# Schematic_-_Power_Driver.net
KiCad netlist of a schematic drawn in Altium Designer
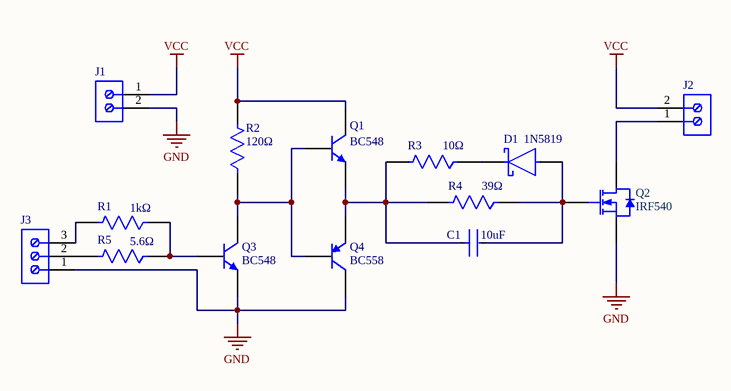
[diagram p0: Schematic - Power Driver.SchDoc]

(export (version "E")
  (design (tool "Eeschema 10.0.6"))
  (components
    (comp (ref "C1")
      (value "10uF")
      (footprint "FP-BFC233860472-MFG")
      (description "CAP FILM 4700PF 20% 1KVDC RADIAL")
      (fields (field (name "VOLTAGE") "300V") (field (name "TOLERANCE") "5%"))
      (libsource (lib "Altium Content Vault") (part "02cd4be3c70576c341d710602a673aa"))
    )
    (comp (ref "D1")
      (value "1N5819")
      (footprint "FP-1N5819-E3-54-MFG")
      (description "DIODE SCHOTTKY 40V 1A DO204AL")
      (fields (field (name "VOLTAGE") "40V"))
      (libsource (lib "Altium Content Vault") (part "1d6ec82d83fb6aee721767c19dac4b9"))
    )
    (comp (ref "J1")
      (value "1725656")
      (footprint "PHOE-1725656-2")
      (description "Male Header, Pitch 2.54 mm, 1 x 2 Position, Height 9 mm, Tail Length 3.5 mm")
      (fields (field (name "MANUFACTURER") "Phoenix Contact"))
      (libsource (lib "Altium Content Vault") (part "CN-1P-F-TB2"))
    )
    (comp (ref "J2")
      (value "1725656")
      (footprint "PHOE-1725656-2")
      (description "Male Header, Pitch 2.54 mm, 1 x 2 Position, Height 9 mm, Tail Length 3.5 mm")
      (fields (field (name "MANUFACTURER") "Phoenix Contact"))
      (libsource (lib "Altium Content Vault") (part "CN-1P-F-TB2"))
    )
    (comp (ref "J3")
      (value "691214110003")
      (footprint "691214110003")
      (fields (field (name "VOLTAGE") "300V"))
      (libsource (lib "Altium Content Vault") (part "TBL - 1R - 03P - Screw"))
    )
    (comp (ref "Q1")
      (value "BC548")
      (footprint "ONSC-TO-92-3-29-11_AM_BL")
      (description "Amplifier Transistor, NPN Silicon, 3-Pin TO-92, Pb-Free, Tape and Reel")
      (fields (field (name "MANUFACTURER") "On Semiconductor") (field (name "PARTNUMBER") "BC548BRL1G"))
      (libsource (lib "Altium Content Vault") (part "ONSC-NPN-C1B2E3-3"))
    )
    (comp (ref "Q2")
      (value "IRF540")
      (footprint "VISH-TO-220AB-3_A")
      (description "Power MOSFET, 100 VDS, -55 to 175 degC, 3-Pin TO-220AB, RoHS, Tube")
      (fields (field (name "MANUFACTURER") "Vishay"))
      (libsource (lib "Altium Content Vault") (part "NEMOS-GDS-3"))
    )
    (comp (ref "Q3")
      (value "BC548")
      (footprint "ONSC-TO-92-3-29-11_AM_BL")
      (description "Amplifier Transistor, NPN Silicon, 3-Pin TO-92, Pb-Free, Tape and Reel")
      (fields (field (name "MANUFACTURER") "On Semiconductor") (field (name "PARTNUMBER") "BC548BRL1G"))
      (libsource (lib "Altium Content Vault") (part "ONSC-NPN-C1B2E3-3"))
    )
    (comp (ref "Q4")
      (value "BC558")
      (footprint "ONSC-TO-92-3-29-11_AM_BL")
      (description "Amplifier Transistor, PNP Silicon, 3-Pin TO-92, Pb-Free, Tape and Reel")
      (fields (field (name "MANUFACTURER") "On Semiconductor") (field (name "PARTNUMBER") "BC558BRL1G"))
      (libsource (lib "Altium Content Vault") (part "ONSC-PNP-C1B2E3-3"))
    )
    (comp (ref "R1")
      (value "1kΩ")
      (footprint "FP-CF14-MFG")
      (description "RES 7.5K OHM 1/4W 5% AXIAL")
      (fields (field (name "TOLERANCE") "5%"))
      (libsource (lib "Altium Content Vault") (part "1029c3af85768c4190bb7ad29bc67b5"))
    )
    (comp (ref "R2")
      (value "120Ω")
      (footprint "FP-CF14-MFG")
      (description "RES 7.5K OHM 1/4W 5% AXIAL")
      (fields (field (name "TOLERANCE") "5%"))
      (libsource (lib "Altium Content Vault") (part "1029c3af85768c4190bb7ad29bc67b5"))
    )
    (comp (ref "R3")
      (value "10Ω")
      (footprint "FP-CF14-MFG")
      (description "RES 7.5K OHM 1/4W 5% AXIAL")
      (fields (field (name "TOLERANCE") "5%"))
      (libsource (lib "Altium Content Vault") (part "1029c3af85768c4190bb7ad29bc67b5"))
    )
    (comp (ref "R4")
      (value "39Ω")
      (footprint "FP-CF14-MFG")
      (description "RES 7.5K OHM 1/4W 5% AXIAL")
      (fields (field (name "TOLERANCE") "5%"))
      (libsource (lib "Altium Content Vault") (part "1029c3af85768c4190bb7ad29bc67b5"))
    )
    (comp (ref "R5")
      (value "5.6Ω")
      (footprint "FP-CF14-MFG")
      (description "RES 7.5K OHM 1/4W 5% AXIAL")
      (fields (field (name "TOLERANCE") "5%"))
      (libsource (lib "Altium Content Vault") (part "1029c3af85768c4190bb7ad29bc67b5"))
    )
  )
  (nets
    (net (code "1") (name "GND") (class "Default")
      (node (ref "J1") (pin "2") (pinfunction "1_2") (pintype "passive"))
      (node (ref "J3") (pin "1") (pinfunction "1_1") (pintype "passive"))
      (node (ref "Q2") (pin "3") (pinfunction "S_3") (pintype "passive"))
      (node (ref "Q3") (pin "3") (pinfunction "E_3") (pintype "passive"))
      (node (ref "Q4") (pin "1") (pinfunction "C_1") (pintype "passive"))
    )
    (net (code "2") (name "Net-(D1-A)") (class "Default")
      (node (ref "C1") (pin "2") (pinfunction "2_2") (pintype "passive"))
      (node (ref "D1") (pin "2") (pinfunction "A_2") (pintype "passive"))
      (node (ref "Q2") (pin "1") (pinfunction "G_1") (pintype "passive"))
      (node (ref "R4") (pin "1") (pinfunction "1_1") (pintype "passive"))
    )
    (net (code "3") (name "Net-(D1-C)") (class "Default")
      (node (ref "D1") (pin "1") (pinfunction "C_1") (pintype "passive"))
      (node (ref "R3") (pin "1") (pinfunction "1_1") (pintype "passive"))
    )
    (net (code "4") (name "Net-(J2-2)") (class "Default")
      (node (ref "J2") (pin "1") (pinfunction "2_1") (pintype "passive"))
      (node (ref "Q2") (pin "2") (pinfunction "D_2") (pintype "passive"))
    )
    (net (code "5") (name "Net-(J3-Pad2)") (class "Default")
      (node (ref "J3") (pin "2") (pinfunction "2_2") (pintype "passive"))
      (node (ref "R5") (pin "2") (pinfunction "2_2") (pintype "passive"))
    )
    (net (code "6") (name "Net-(J3-Pad3)") (class "Default")
      (node (ref "J3") (pin "3") (pinfunction "3_3") (pintype "passive"))
      (node (ref "R1") (pin "2") (pinfunction "2_2") (pintype "passive"))
    )
    (net (code "7") (name "Net-(Q1-B)") (class "Default")
      (node (ref "Q1") (pin "2") (pinfunction "B_2") (pintype "passive"))
      (node (ref "Q3") (pin "1") (pinfunction "C_1") (pintype "passive"))
      (node (ref "Q4") (pin "2") (pinfunction "B_2") (pintype "passive"))
      (node (ref "R2") (pin "1") (pinfunction "1_1") (pintype "passive"))
    )
    (net (code "8") (name "Net-(Q1-E)") (class "Default")
      (node (ref "C1") (pin "1") (pinfunction "1_1") (pintype "passive"))
      (node (ref "Q1") (pin "3") (pinfunction "E_3") (pintype "passive"))
      (node (ref "Q4") (pin "3") (pinfunction "E_3") (pintype "passive"))
      (node (ref "R3") (pin "2") (pinfunction "2_2") (pintype "passive"))
      (node (ref "R4") (pin "2") (pinfunction "2_2") (pintype "passive"))
    )
    (net (code "9") (name "Net-(Q3-B)") (class "Default")
      (node (ref "Q3") (pin "2") (pinfunction "B_2") (pintype "passive"))
      (node (ref "R1") (pin "1") (pinfunction "1_1") (pintype "passive"))
      (node (ref "R5") (pin "1") (pinfunction "1_1") (pintype "passive"))
    )
    (net (code "10") (name "VCC") (class "Default")
      (node (ref "J1") (pin "1") (pinfunction "2_1") (pintype "passive"))
      (node (ref "J2") (pin "2") (pinfunction "1_2") (pintype "passive"))
      (node (ref "Q1") (pin "1") (pinfunction "C_1") (pintype "passive"))
      (node (ref "R2") (pin "2") (pinfunction "2_2") (pintype "passive"))
    )
  )
)
